# BORD3.net
KiCad netlist of a schematic drawn in EAGLE
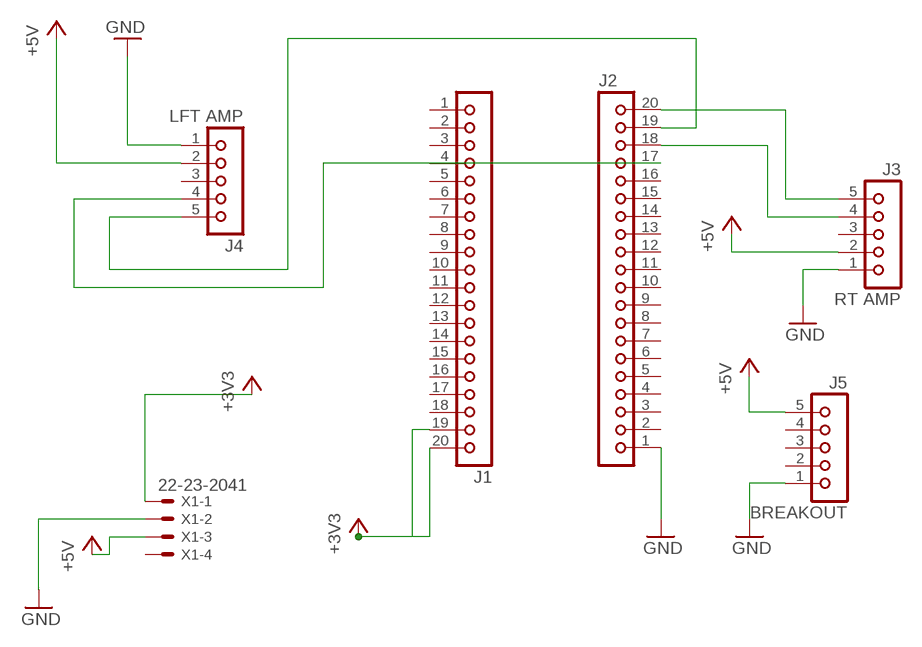
[diagram p0: schematic, sheet 1]

(export (version "E")
  (design (tool "Eeschema 10.0.6"))
  (components
    (comp (ref "J1")
      (value "JBK20")
      (footprint "eagle-import:JBK20")
      (libsource (lib "eagle-import") (part "JBK20"))
    )
    (comp (ref "J2")
      (value "JBK20")
      (footprint "eagle-import:JBK20")
      (libsource (lib "eagle-import") (part "JBK20"))
    )
    (comp (ref "J3")
      (value "RT AMP")
      (footprint "eagle-import:JU05")
      (libsource (lib "eagle-import") (part "JU05"))
    )
    (comp (ref "J4")
      (value "LFT AMP")
      (footprint "eagle-import:JU05")
      (libsource (lib "eagle-import") (part "JU05"))
    )
    (comp (ref "J5")
      (value "BREAKOUT")
      (footprint "eagle-import:JU05")
      (libsource (lib "eagle-import") (part "JU05"))
    )
    (comp (ref "X1")
      (value "22-23-2041")
      (footprint "eagle-import:22-23-2041")
      (fields (field (name "MF") "MOLEX"))
      (libsource (lib "eagle-import") (part "22-23-2041"))
    )
  )
  (nets
    (net (code "1") (name "+3V3") (class "Default")
      (node (ref "J1") (pin "19") (pinfunction "19_19") (pintype "passive"))
      (node (ref "J1") (pin "20") (pinfunction "20_20") (pintype "passive"))
      (node (ref "X1") (pin "1") (pinfunction "S_1") (pintype "passive"))
    )
    (net (code "2") (name "+5V") (class "Default")
      (node (ref "J3") (pin "2") (pinfunction "2_2") (pintype "passive"))
      (node (ref "J4") (pin "2") (pinfunction "2_2") (pintype "passive"))
      (node (ref "J5") (pin "5") (pinfunction "5_5") (pintype "passive"))
      (node (ref "X1") (pin "3") (pinfunction "S_3") (pintype "passive"))
    )
    (net (code "3") (name "GND") (class "Default")
      (node (ref "J2") (pin "1") (pinfunction "1_1") (pintype "passive"))
      (node (ref "J3") (pin "1") (pinfunction "1_1") (pintype "passive"))
      (node (ref "J4") (pin "1") (pinfunction "1_1") (pintype "passive"))
      (node (ref "J5") (pin "1") (pinfunction "1_1") (pintype "passive"))
      (node (ref "X1") (pin "2") (pinfunction "S_2") (pintype "passive"))
    )
    (net (code "4") (name "Net-(J2-Pad17)") (class "Default")
      (node (ref "J2") (pin "17") (pinfunction "17_17") (pintype "passive"))
      (node (ref "J4") (pin "4") (pinfunction "4_4") (pintype "passive"))
    )
    (net (code "5") (name "Net-(J2-Pad18)") (class "Default")
      (node (ref "J2") (pin "18") (pinfunction "18_18") (pintype "passive"))
      (node (ref "J3") (pin "4") (pinfunction "4_4") (pintype "passive"))
    )
    (net (code "6") (name "Net-(J2-Pad19)") (class "Default")
      (node (ref "J2") (pin "19") (pinfunction "19_19") (pintype "passive"))
      (node (ref "J4") (pin "5") (pinfunction "5_5") (pintype "passive"))
    )
    (net (code "7") (name "Net-(J2-Pad20)") (class "Default")
      (node (ref "J2") (pin "20") (pinfunction "20_20") (pintype "passive"))
      (node (ref "J3") (pin "5") (pinfunction "5_5") (pintype "passive"))
    )
    (net (code "8") (name "unconnected-(J1-Pad1)") (class "Default")
      (node (ref "J1") (pin "1") (pinfunction "1_1") (pintype "passive"))
    )
    (net (code "9") (name "unconnected-(J1-Pad2)") (class "Default")
      (node (ref "J1") (pin "2") (pinfunction "2_2") (pintype "passive"))
    )
    (net (code "10") (name "unconnected-(J1-Pad3)") (class "Default")
      (node (ref "J1") (pin "3") (pinfunction "3_3") (pintype "passive"))
    )
    (net (code "11") (name "unconnected-(J1-Pad4)") (class "Default")
      (node (ref "J1") (pin "4") (pinfunction "4_4") (pintype "passive"))
    )
    (net (code "12") (name "unconnected-(J1-Pad5)") (class "Default")
      (node (ref "J1") (pin "5") (pinfunction "5_5") (pintype "passive"))
    )
    (net (code "13") (name "unconnected-(J1-Pad6)") (class "Default")
      (node (ref "J1") (pin "6") (pinfunction "6_6") (pintype "passive"))
    )
    (net (code "14") (name "unconnected-(J1-Pad7)") (class "Default")
      (node (ref "J1") (pin "7") (pinfunction "7_7") (pintype "passive"))
    )
    (net (code "15") (name "unconnected-(J1-Pad8)") (class "Default")
      (node (ref "J1") (pin "8") (pinfunction "8_8") (pintype "passive"))
    )
    (net (code "16") (name "unconnected-(J1-Pad9)") (class "Default")
      (node (ref "J1") (pin "9") (pinfunction "9_9") (pintype "passive"))
    )
    (net (code "17") (name "unconnected-(J1-Pad10)") (class "Default")
      (node (ref "J1") (pin "10") (pinfunction "10_10") (pintype "passive"))
    )
    (net (code "18") (name "unconnected-(J1-Pad11)") (class "Default")
      (node (ref "J1") (pin "11") (pinfunction "11_11") (pintype "passive"))
    )
    (net (code "19") (name "unconnected-(J1-Pad12)") (class "Default")
      (node (ref "J1") (pin "12") (pinfunction "12_12") (pintype "passive"))
    )
    (net (code "20") (name "unconnected-(J1-Pad13)") (class "Default")
      (node (ref "J1") (pin "13") (pinfunction "13_13") (pintype "passive"))
    )
    (net (code "21") (name "unconnected-(J1-Pad14)") (class "Default")
      (node (ref "J1") (pin "14") (pinfunction "14_14") (pintype "passive"))
    )
    (net (code "22") (name "unconnected-(J1-Pad15)") (class "Default")
      (node (ref "J1") (pin "15") (pinfunction "15_15") (pintype "passive"))
    )
    (net (code "23") (name "unconnected-(J1-Pad16)") (class "Default")
      (node (ref "J1") (pin "16") (pinfunction "16_16") (pintype "passive"))
    )
    (net (code "24") (name "unconnected-(J1-Pad17)") (class "Default")
      (node (ref "J1") (pin "17") (pinfunction "17_17") (pintype "passive"))
    )
    (net (code "25") (name "unconnected-(J1-Pad18)") (class "Default")
      (node (ref "J1") (pin "18") (pinfunction "18_18") (pintype "passive"))
    )
    (net (code "26") (name "unconnected-(J2-Pad2)") (class "Default")
      (node (ref "J2") (pin "2") (pinfunction "2_2") (pintype "passive"))
    )
    (net (code "27") (name "unconnected-(J2-Pad3)") (class "Default")
      (node (ref "J2") (pin "3") (pinfunction "3_3") (pintype "passive"))
    )
    (net (code "28") (name "unconnected-(J2-Pad4)") (class "Default")
      (node (ref "J2") (pin "4") (pinfunction "4_4") (pintype "passive"))
    )
    (net (code "29") (name "unconnected-(J2-Pad5)") (class "Default")
      (node (ref "J2") (pin "5") (pinfunction "5_5") (pintype "passive"))
    )
    (net (code "30") (name "unconnected-(J2-Pad6)") (class "Default")
      (node (ref "J2") (pin "6") (pinfunction "6_6") (pintype "passive"))
    )
    (net (code "31") (name "unconnected-(J2-Pad7)") (class "Default")
      (node (ref "J2") (pin "7") (pinfunction "7_7") (pintype "passive"))
    )
    (net (code "32") (name "unconnected-(J2-Pad8)") (class "Default")
      (node (ref "J2") (pin "8") (pinfunction "8_8") (pintype "passive"))
    )
    (net (code "33") (name "unconnected-(J2-Pad9)") (class "Default")
      (node (ref "J2") (pin "9") (pinfunction "9_9") (pintype "passive"))
    )
    (net (code "34") (name "unconnected-(J2-Pad10)") (class "Default")
      (node (ref "J2") (pin "10") (pinfunction "10_10") (pintype "passive"))
    )
    (net (code "35") (name "unconnected-(J2-Pad11)") (class "Default")
      (node (ref "J2") (pin "11") (pinfunction "11_11") (pintype "passive"))
    )
    (net (code "36") (name "unconnected-(J2-Pad12)") (class "Default")
      (node (ref "J2") (pin "12") (pinfunction "12_12") (pintype "passive"))
    )
    (net (code "37") (name "unconnected-(J2-Pad13)") (class "Default")
      (node (ref "J2") (pin "13") (pinfunction "13_13") (pintype "passive"))
    )
    (net (code "38") (name "unconnected-(J2-Pad14)") (class "Default")
      (node (ref "J2") (pin "14") (pinfunction "14_14") (pintype "passive"))
    )
    (net (code "39") (name "unconnected-(J2-Pad15)") (class "Default")
      (node (ref "J2") (pin "15") (pinfunction "15_15") (pintype "passive"))
    )
    (net (code "40") (name "unconnected-(J2-Pad16)") (class "Default")
      (node (ref "J2") (pin "16") (pinfunction "16_16") (pintype "passive"))
    )
    (net (code "41") (name "unconnected-(J3-Pad3)") (class "Default")
      (node (ref "J3") (pin "3") (pinfunction "3_3") (pintype "passive"))
    )
    (net (code "42") (name "unconnected-(J4-Pad3)") (class "Default")
      (node (ref "J4") (pin "3") (pinfunction "3_3") (pintype "passive"))
    )
    (net (code "43") (name "unconnected-(J5-Pad2)") (class "Default")
      (node (ref "J5") (pin "2") (pinfunction "2_2") (pintype "passive"))
    )
    (net (code "44") (name "unconnected-(J5-Pad3)") (class "Default")
      (node (ref "J5") (pin "3") (pinfunction "3_3") (pintype "passive"))
    )
    (net (code "45") (name "unconnected-(J5-Pad4)") (class "Default")
      (node (ref "J5") (pin "4") (pinfunction "4_4") (pintype "passive"))
    )
    (net (code "46") (name "unconnected-(X1D-S-Pad4)") (class "Default")
      (node (ref "X1") (pin "4") (pinfunction "S_4") (pintype "passive"))
    )
  )
)
